# Timing_Unit.net
KiCad netlist of a schematic drawn in Altium Designer
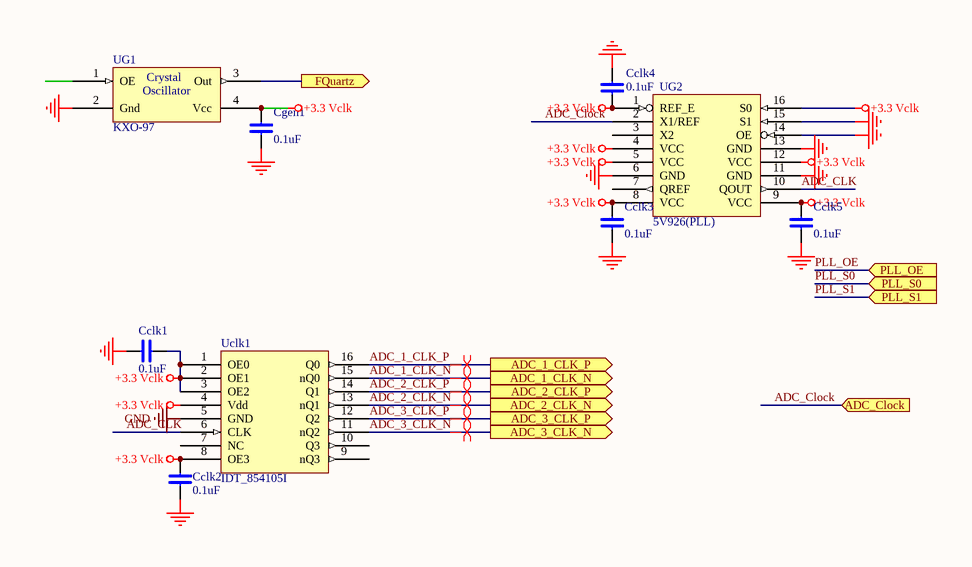
[diagram p0: Timing Unit.SchDoc]

(export (version "E")
  (design (tool "Eeschema 10.0.6"))
  (components
    (comp (ref "Cclk1") (value "0.1uF") (footprint "chip0603") (libsource (lib "*") (part "C")))
    (comp (ref "Cclk2") (value "0.1uF") (footprint "chip0603") (libsource (lib "*") (part "C")))
    (comp (ref "Cclk3") (value "0.1uF") (footprint "chip0603") (libsource (lib "*") (part "C")))
    (comp (ref "Cclk4") (value "0.1uF") (footprint "chip0603") (libsource (lib "*") (part "C")))
    (comp (ref "Cclk5") (value "0.1uF") (footprint "chip0603") (libsource (lib "*") (part "C")))
    (comp (ref "Cgen1") (value "0.1uF") (footprint "chip0603") (libsource (lib "*") (part "C")))
    (comp (ref "Uclk1")
      (value "IDT_854105I")
      (footprint "TSSOP16")
      (libsource (lib "Backup of Mylib") (part "IDT_854105I"))
    )
    (comp (ref "UG1")
      (value "KXO-97")
      (footprint "SG-636")
      (description "Crystal Oscillator (SMD)")
      (libsource (lib "*") (part "SG-636"))
    )
    (comp (ref "UG2")
      (value "5V926(PLL)")
      (footprint "TSSOP16")
      (libsource (lib "Backup of Mylib") (part "5V926(PLL)"))
    )
  )
  (nets
    (net (code "1") (name "+3.3 Vclk") (class "Default")
      (node (ref "Cclk1") (pin "2") (pinfunction "2_2") (pintype "passive"))
      (node (ref "Cclk2") (pin "2") (pinfunction "2_2") (pintype "passive"))
      (node (ref "Cclk3") (pin "2") (pinfunction "2_2") (pintype "passive"))
      (node (ref "Cclk4") (pin "2") (pinfunction "2_2") (pintype "passive"))
      (node (ref "Cclk5") (pin "2") (pinfunction "2_2") (pintype "passive"))
      (node (ref "Cgen1") (pin "2") (pinfunction "2_2") (pintype "passive"))
      (node (ref "UG1") (pin "4") (pinfunction "Vcc_4") (pintype "power_in"))
      (node (ref "UG2") (pin "1") (pinfunction "REF_E_1") (pintype "input"))
      (node (ref "UG2") (pin "12") (pinfunction "VCC_12") (pintype "power_in"))
      (node (ref "UG2") (pin "16") (pinfunction "S0_16") (pintype "input"))
      (node (ref "UG2") (pin "4") (pinfunction "VCC_4") (pintype "power_in"))
      (node (ref "UG2") (pin "5") (pinfunction "VCC_5") (pintype "power_in"))
      (node (ref "UG2") (pin "8") (pinfunction "VCC_8") (pintype "power_in"))
      (node (ref "UG2") (pin "9") (pinfunction "VCC_9") (pintype "power_in"))
      (node (ref "Uclk1") (pin "1") (pinfunction "OE0_1") (pintype "passive"))
      (node (ref "Uclk1") (pin "2") (pinfunction "OE1_2") (pintype "passive"))
      (node (ref "Uclk1") (pin "3") (pinfunction "OE2_3") (pintype "passive"))
      (node (ref "Uclk1") (pin "4") (pinfunction "Vdd_4") (pintype "power_in"))
      (node (ref "Uclk1") (pin "8") (pinfunction "OE3_8") (pintype "passive"))
    )
    (net (code "2") (name "/ADC_1_CLK_N") (class "Default")
      (node (ref "Uclk1") (pin "15") (pinfunction "nQ0_15") (pintype "output"))
    )
    (net (code "3") (name "/ADC_1_CLK_P") (class "Default")
      (node (ref "Uclk1") (pin "16") (pinfunction "Q0_16") (pintype "output"))
    )
    (net (code "4") (name "/ADC_2_CLK_N") (class "Default")
      (node (ref "Uclk1") (pin "13") (pinfunction "nQ1_13") (pintype "output"))
    )
    (net (code "5") (name "/ADC_2_CLK_P") (class "Default")
      (node (ref "Uclk1") (pin "14") (pinfunction "Q1_14") (pintype "output"))
    )
    (net (code "6") (name "/ADC_3_CLK_N") (class "Default")
      (node (ref "Uclk1") (pin "11") (pinfunction "nQ2_11") (pintype "output"))
    )
    (net (code "7") (name "/ADC_3_CLK_P") (class "Default")
      (node (ref "Uclk1") (pin "12") (pinfunction "Q2_12") (pintype "output"))
    )
    (net (code "8") (name "/ADC_CLK") (class "Default")
      (node (ref "UG2") (pin "10") (pinfunction "QOUT_10") (pintype "output"))
      (node (ref "Uclk1") (pin "6") (pinfunction "CLK_6") (pintype "input"))
    )
    (net (code "9") (name "/ADC_Clock") (class "Default")
      (node (ref "UG2") (pin "2") (pinfunction "X1/REF_2") (pintype "passive"))
    )
    (net (code "10") (name "/FQuartz") (class "Default")
      (node (ref "UG1") (pin "3") (pinfunction "Out_3") (pintype "output"))
    )
    (net (code "14") (name "GND") (class "Default")
      (node (ref "Cclk1") (pin "1") (pinfunction "1_1") (pintype "passive"))
      (node (ref "Cclk2") (pin "1") (pinfunction "1_1") (pintype "passive"))
      (node (ref "Cclk3") (pin "1") (pinfunction "1_1") (pintype "passive"))
      (node (ref "Cclk4") (pin "1") (pinfunction "1_1") (pintype "passive"))
      (node (ref "Cclk5") (pin "1") (pinfunction "1_1") (pintype "passive"))
      (node (ref "Cgen1") (pin "1") (pinfunction "1_1") (pintype "passive"))
      (node (ref "UG1") (pin "2") (pinfunction "Gnd_2") (pintype "power_in"))
      (node (ref "UG2") (pin "11") (pinfunction "GND_11") (pintype "power_in"))
      (node (ref "UG2") (pin "13") (pinfunction "GND_13") (pintype "power_in"))
      (node (ref "UG2") (pin "14") (pinfunction "OE_14") (pintype "input"))
      (node (ref "UG2") (pin "15") (pinfunction "S1_15") (pintype "input"))
      (node (ref "UG2") (pin "6") (pinfunction "GND_6") (pintype "power_in"))
      (node (ref "Uclk1") (pin "5") (pinfunction "GND_5") (pintype "power_in"))
    )
    (net (code "15") (name "unconnected-(UG1-OE-Pad1)") (class "Default")
      (node (ref "UG1") (pin "1") (pinfunction "OE_1") (pintype "input"))
    )
    (net (code "16") (name "unconnected-(UG2-QREF-Pad7)") (class "Default")
      (node (ref "UG2") (pin "7") (pinfunction "QREF_7") (pintype "output"))
    )
    (net (code "17") (name "unconnected-(UG2-X2-Pad3)") (class "Default")
      (node (ref "UG2") (pin "3") (pinfunction "X2_3") (pintype "passive"))
    )
    (net (code "18") (name "unconnected-(Uclk1-NC-Pad7)") (class "Default")
      (node (ref "Uclk1") (pin "7") (pinfunction "NC_7") (pintype "passive"))
    )
    (net (code "19") (name "unconnected-(Uclk1-Q3-Pad10)") (class "Default")
      (node (ref "Uclk1") (pin "10") (pinfunction "Q3_10") (pintype "output"))
    )
    (net (code "20") (name "unconnected-(Uclk1-nQ3-Pad9)") (class "Default")
      (node (ref "Uclk1") (pin "9") (pinfunction "nQ3_9") (pintype "output"))
    )
  )
)
